# 05_IO.net
KiCad netlist of a schematic drawn in Altium Designer
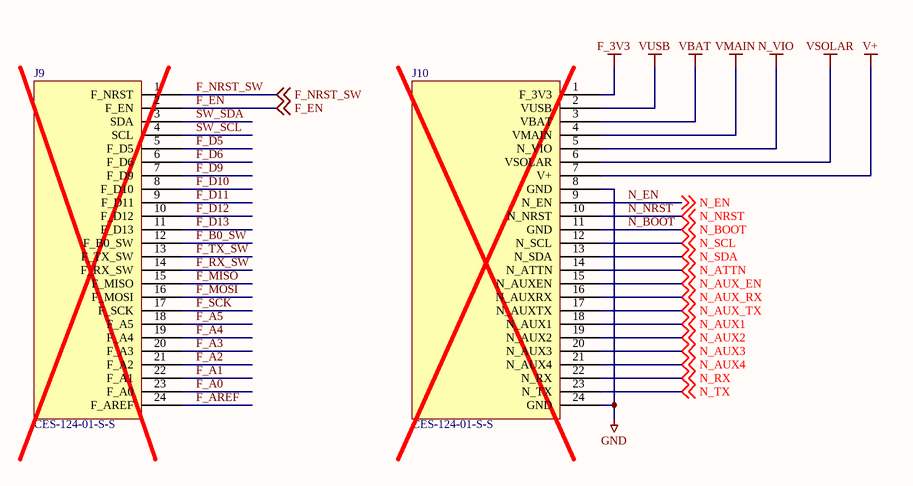
[diagram p0: 05_IO.SchDoc]

(export (version "E")
  (design (tool "Eeschema 10.0.6"))
  (components
    (comp (ref "J9")
      (value "CES-124-01-S-S")
      (footprint "CES-124-01-S-S")
      (description "24x1 0.1\" pitch half height female header")
      (fields
        (field (name "MANUFACTURER") "Samtec Inc.")
        (field (name "BL PART NUMBER") "2007-465")
        (field (name "DRAWN_BY") "Blues Wireless")
      )
      (libsource (lib "n21-p2") (part "SIDECON"))
    )
    (comp (ref "J10")
      (value "CES-124-01-S-S")
      (footprint "CES-124-01-S-S")
      (description "24x1 0.1\" pitch half height female header")
      (fields
        (field (name "MANUFACTURER") "Samtec Inc.")
        (field (name "BL PART NUMBER") "2007-465")
        (field (name "DRAWN_BY") "Blues Wireless")
      )
      (libsource (lib "n21-p2") (part "SIDECON_N"))
    )
  )
  (nets
    (net (code "1") (name "/F_A0") (class "Default")
      (node (ref "J9") (pin "23") (pinfunction "F_A0_23") (pintype "passive"))
    )
    (net (code "2") (name "/F_A1") (class "Default")
      (node (ref "J9") (pin "22") (pinfunction "F_A1_22") (pintype "passive"))
    )
    (net (code "3") (name "/F_A2") (class "Default")
      (node (ref "J9") (pin "21") (pinfunction "F_A2_21") (pintype "passive"))
    )
    (net (code "4") (name "/F_A3") (class "Default")
      (node (ref "J9") (pin "20") (pinfunction "F_A3_20") (pintype "passive"))
    )
    (net (code "5") (name "/F_A4") (class "Default")
      (node (ref "J9") (pin "19") (pinfunction "F_A4_19") (pintype "passive"))
    )
    (net (code "6") (name "/F_A5") (class "Default")
      (node (ref "J9") (pin "18") (pinfunction "F_A5_18") (pintype "passive"))
    )
    (net (code "7") (name "/F_AREF") (class "Default")
      (node (ref "J9") (pin "24") (pinfunction "F_AREF_24") (pintype "passive"))
    )
    (net (code "8") (name "/F_B0_SW") (class "Default")
      (node (ref "J9") (pin "12") (pinfunction "F_B0_SW_12") (pintype "passive"))
    )
    (net (code "9") (name "/F_D5") (class "Default")
      (node (ref "J9") (pin "5") (pinfunction "F_D5_5") (pintype "passive"))
    )
    (net (code "10") (name "/F_D6") (class "Default")
      (node (ref "J9") (pin "6") (pinfunction "F_D6_6") (pintype "passive"))
    )
    (net (code "11") (name "/F_D9") (class "Default")
      (node (ref "J9") (pin "7") (pinfunction "F_D9_7") (pintype "passive"))
    )
    (net (code "12") (name "/F_D10") (class "Default")
      (node (ref "J9") (pin "8") (pinfunction "F_D10_8") (pintype "passive"))
    )
    (net (code "13") (name "/F_D11") (class "Default")
      (node (ref "J9") (pin "9") (pinfunction "F_D11_9") (pintype "passive"))
    )
    (net (code "14") (name "/F_D12") (class "Default")
      (node (ref "J9") (pin "10") (pinfunction "F_D12_10") (pintype "passive"))
    )
    (net (code "15") (name "/F_D13") (class "Default")
      (node (ref "J9") (pin "11") (pinfunction "F_D13_11") (pintype "passive"))
    )
    (net (code "16") (name "/F_MISO") (class "Default")
      (node (ref "J9") (pin "15") (pinfunction "F_MISO_15") (pintype "passive"))
    )
    (net (code "17") (name "/F_MOSI") (class "Default")
      (node (ref "J9") (pin "16") (pinfunction "F_MOSI_16") (pintype "passive"))
    )
    (net (code "18") (name "/F_RX_SW") (class "Default")
      (node (ref "J9") (pin "14") (pinfunction "F_RX_SW_14") (pintype "passive"))
    )
    (net (code "19") (name "/F_SCK") (class "Default")
      (node (ref "J9") (pin "17") (pinfunction "F_SCK_17") (pintype "passive"))
    )
    (net (code "20") (name "/F_TX_SW") (class "Default")
      (node (ref "J9") (pin "13") (pinfunction "F_TX_SW_13") (pintype "passive"))
    )
    (net (code "21") (name "/SW_SCL") (class "Default")
      (node (ref "J9") (pin "4") (pinfunction "SCL_4") (pintype "passive"))
    )
    (net (code "22") (name "/SW_SDA") (class "Default")
      (node (ref "J9") (pin "3") (pinfunction "SDA_3") (pintype "passive"))
    )
    (net (code "23") (name "F_3V3") (class "Default")
      (node (ref "J10") (pin "1") (pinfunction "F_3V3_1") (pintype "passive"))
    )
    (net (code "24") (name "F_EN") (class "Default")
      (node (ref "J9") (pin "2") (pinfunction "F_EN_2") (pintype "passive"))
    )
    (net (code "25") (name "F_NRST_SW") (class "Default")
      (node (ref "J9") (pin "1") (pinfunction "F_NRST_1") (pintype "passive"))
    )
    (net (code "26") (name "GND") (class "Default")
      (node (ref "J10") (pin "24") (pinfunction "GND_24") (pintype "passive"))
      (node (ref "J10") (pin "8") (pinfunction "GND_8") (pintype "passive"))
    )
    (net (code "27") (name "N_ATTN") (class "Default")
      (node (ref "J10") (pin "14") (pinfunction "N_ATTN_14") (pintype "passive"))
    )
    (net (code "28") (name "N_AUX1") (class "Default")
      (node (ref "J10") (pin "18") (pinfunction "N_AUX1_18") (pintype "passive"))
    )
    (net (code "29") (name "N_AUX2") (class "Default")
      (node (ref "J10") (pin "19") (pinfunction "N_AUX2_19") (pintype "passive"))
    )
    (net (code "30") (name "N_AUX3") (class "Default")
      (node (ref "J10") (pin "20") (pinfunction "N_AUX3_20") (pintype "passive"))
    )
    (net (code "31") (name "N_AUX4") (class "Default")
      (node (ref "J10") (pin "21") (pinfunction "N_AUX4_21") (pintype "passive"))
    )
    (net (code "32") (name "N_AUX_EN") (class "Default")
      (node (ref "J10") (pin "15") (pinfunction "N_AUXEN_15") (pintype "passive"))
    )
    (net (code "33") (name "N_AUX_RX") (class "Default")
      (node (ref "J10") (pin "16") (pinfunction "N_AUXRX_16") (pintype "passive"))
    )
    (net (code "34") (name "N_AUX_TX") (class "Default")
      (node (ref "J10") (pin "17") (pinfunction "N_AUXTX_17") (pintype "passive"))
    )
    (net (code "35") (name "N_BOOT") (class "Default")
      (node (ref "J10") (pin "11") (pinfunction "GND_11") (pintype "passive"))
    )
    (net (code "36") (name "N_EN") (class "Default")
      (node (ref "J10") (pin "9") (pinfunction "N_EN_9") (pintype "passive"))
    )
    (net (code "37") (name "N_NRST") (class "Default")
      (node (ref "J10") (pin "10") (pinfunction "N_NRST_10") (pintype "passive"))
    )
    (net (code "38") (name "N_RX") (class "Default")
      (node (ref "J10") (pin "22") (pinfunction "N_RX_22") (pintype "passive"))
    )
    (net (code "39") (name "N_SCL") (class "Default")
      (node (ref "J10") (pin "12") (pinfunction "N_SCL_12") (pintype "passive"))
    )
    (net (code "40") (name "N_SDA") (class "Default")
      (node (ref "J10") (pin "13") (pinfunction "N_SDA_13") (pintype "passive"))
    )
    (net (code "41") (name "N_TX") (class "Default")
      (node (ref "J10") (pin "23") (pinfunction "N_TX_23") (pintype "passive"))
    )
    (net (code "42") (name "N_VIO") (class "Default")
      (node (ref "J10") (pin "5") (pinfunction "N_VIO_5") (pintype "passive"))
    )
    (net (code "43") (name "V+") (class "Default")
      (node (ref "J10") (pin "7") (pinfunction "V+_7") (pintype "passive"))
    )
    (net (code "44") (name "VBAT") (class "Default")
      (node (ref "J10") (pin "3") (pinfunction "VBAT_3") (pintype "passive"))
    )
    (net (code "45") (name "VMAIN") (class "Default")
      (node (ref "J10") (pin "4") (pinfunction "VMAIN_4") (pintype "passive"))
    )
    (net (code "46") (name "VSOLAR") (class "Default")
      (node (ref "J10") (pin "6") (pinfunction "VSOLAR_6") (pintype "passive"))
    )
    (net (code "47") (name "VUSB") (class "Default")
      (node (ref "J10") (pin "2") (pinfunction "VUSB_2") (pintype "passive"))
    )
  )
)
